# rfob.net
KiCad netlist of a schematic drawn in EAGLE
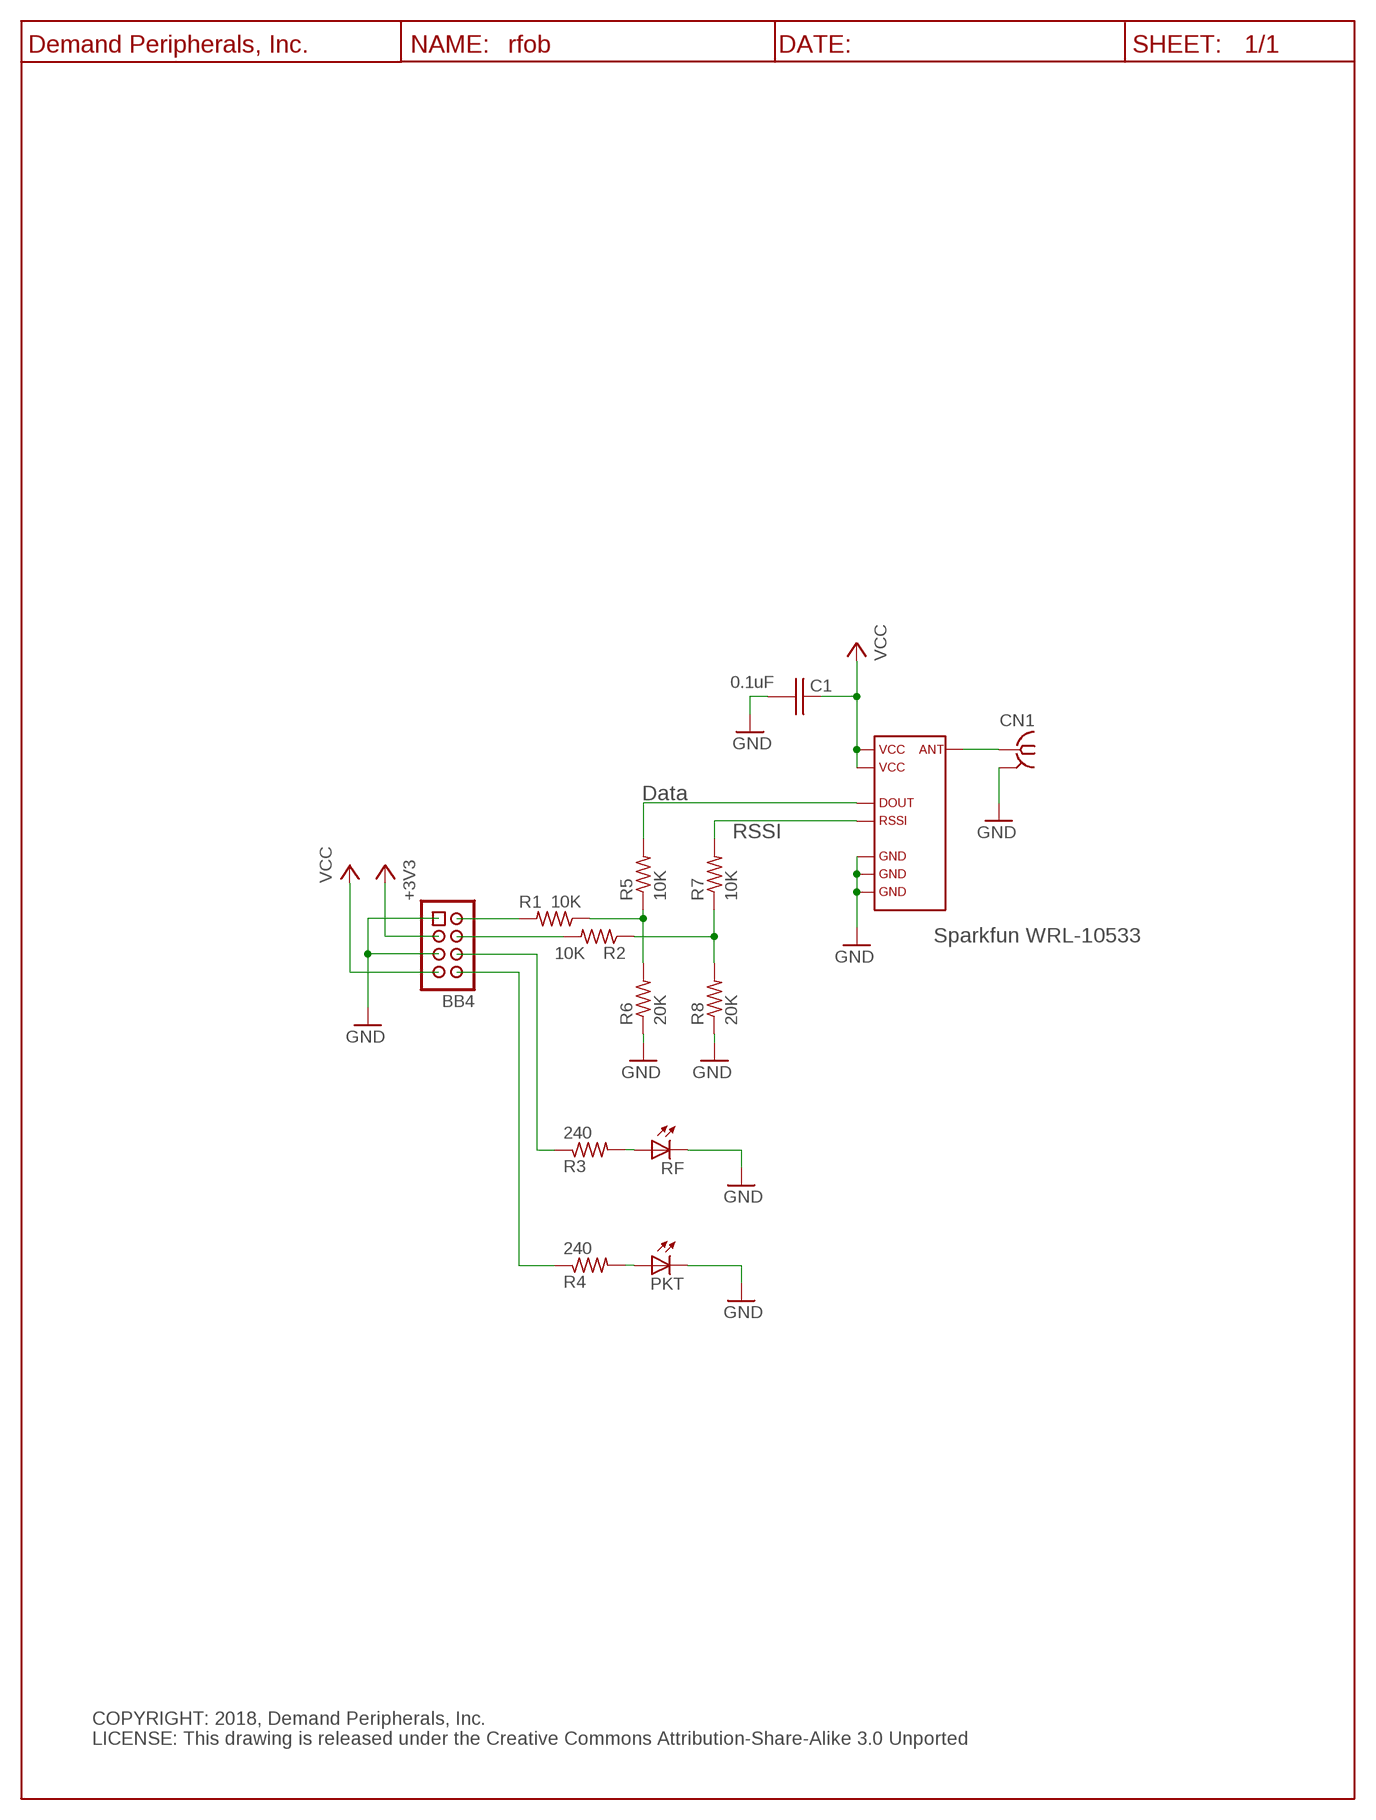
[diagram p0: schematic, sheet 1]

(export (version "E")
  (design (tool "Eeschema 10.0.6"))
  (components
    (comp (ref "BB4")
      (value "Keyed_Pin_Header_4x2(0.1\"x0.1\")")
      (footprint "eagle-import:HDR-4X2")
      (libsource (lib "eagle-import") (part "HDR-4X2-SHR"))
    )
    (comp (ref "C1")
      (value "0.1uF")
      (footprint "eagle-import:C0603")
      (libsource (lib "eagle-import") (part "C0.1UF_C0603"))
    )
    (comp (ref "CN1")
      (value "BU-SMA-V")
      (footprint "eagle-import:BU-SMA-V")
      (libsource (lib "eagle-import") (part "BU-SMA-V"))
    )
    (comp (ref "PKT")
      (value "LED-0805-RED")
      (footprint "eagle-import:0805")
      (libsource (lib "eagle-import") (part "LED-0805-RED"))
    )
    (comp (ref "R1")
      (value "10K")
      (footprint "eagle-import:R0603")
      (libsource (lib "eagle-import") (part "R10K_R0603"))
    )
    (comp (ref "R2")
      (value "10K")
      (footprint "eagle-import:R0603")
      (libsource (lib "eagle-import") (part "R10K_R0603"))
    )
    (comp (ref "R3")
      (value "240")
      (footprint "eagle-import:R0603")
      (libsource (lib "eagle-import") (part "R240_"))
    )
    (comp (ref "R4")
      (value "240")
      (footprint "eagle-import:R0603")
      (libsource (lib "eagle-import") (part "R240_"))
    )
    (comp (ref "R5")
      (value "10K")
      (footprint "eagle-import:R0603")
      (libsource (lib "eagle-import") (part "R10K_R0603"))
    )
    (comp (ref "R6")
      (value "20K")
      (footprint "eagle-import:R0603")
      (libsource (lib "eagle-import") (part "R20K_R0603"))
    )
    (comp (ref "R7")
      (value "10K")
      (footprint "eagle-import:R0603")
      (libsource (lib "eagle-import") (part "R10K_R0603"))
    )
    (comp (ref "R8")
      (value "20K")
      (footprint "eagle-import:R0603")
      (libsource (lib "eagle-import") (part "R20K_R0603"))
    )
    (comp (ref "RF")
      (value "LED-0805-GRN")
      (footprint "eagle-import:0805")
      (libsource (lib "eagle-import") (part "LED-0805-GRN"))
    )
    (comp (ref "RF1")
      (value "RFLINK")
      (footprint "eagle-import:RFLINK")
      (libsource (lib "eagle-import") (part "RFLINK"))
    )
    (comp (ref "U$1")
      (value "DP_FRAME_P")
      (footprint "eagle-import:P_FRAME")
      (libsource (lib "eagle-import") (part "DP_FRAME_P"))
    )
  )
  (nets
    (net (code "1") (name "+3V3") (class "Default")
      (node (ref "BB4") (pin "3") (pinfunction "3_3") (pintype "passive"))
    )
    (net (code "2") (name "GND") (class "Default")
      (node (ref "BB4") (pin "1") (pinfunction "1_1") (pintype "passive"))
      (node (ref "BB4") (pin "5") (pinfunction "5_5") (pintype "passive"))
      (node (ref "C1") (pin "2") (pinfunction "2_2") (pintype "passive"))
      (node (ref "CN1") (pin "2") (pinfunction "2_2") (pintype "passive"))
      (node (ref "CN1") (pin "3") (pinfunction "2_3") (pintype "passive"))
      (node (ref "CN1") (pin "4") (pinfunction "2_4") (pintype "passive"))
      (node (ref "CN1") (pin "5") (pinfunction "2_5") (pintype "passive"))
      (node (ref "PKT") (pin "C") (pinfunction "C_C") (pintype "passive"))
      (node (ref "R6") (pin "1") (pinfunction "1_1") (pintype "passive"))
      (node (ref "R8") (pin "1") (pinfunction "1_1") (pintype "passive"))
      (node (ref "RF") (pin "C") (pinfunction "C_C") (pintype "passive"))
      (node (ref "RF1") (pin "1") (pinfunction "GND1_1") (pintype "open_collector"))
      (node (ref "RF1") (pin "6") (pinfunction "GND3_6") (pintype "open_collector"))
      (node (ref "RF1") (pin "7") (pinfunction "GND2_7") (pintype "open_collector"))
    )
    (net (code "3") (name "Net-(BB4-Pad2)") (class "Default")
      (node (ref "BB4") (pin "2") (pinfunction "2_2") (pintype "passive"))
      (node (ref "R1") (pin "2") (pinfunction "2_2") (pintype "passive"))
    )
    (net (code "4") (name "Net-(BB4-Pad4)") (class "Default")
      (node (ref "BB4") (pin "4") (pinfunction "4_4") (pintype "passive"))
      (node (ref "R2") (pin "2") (pinfunction "2_2") (pintype "passive"))
    )
    (net (code "5") (name "Net-(BB4-Pad6)") (class "Default")
      (node (ref "BB4") (pin "6") (pinfunction "6_6") (pintype "passive"))
      (node (ref "R3") (pin "1") (pinfunction "1_1") (pintype "passive"))
    )
    (net (code "6") (name "Net-(BB4-Pad8)") (class "Default")
      (node (ref "BB4") (pin "8") (pinfunction "8_8") (pintype "passive"))
      (node (ref "R4") (pin "1") (pinfunction "1_1") (pintype "passive"))
    )
    (net (code "7") (name "Net-(PKT-PadA)") (class "Default")
      (node (ref "PKT") (pin "A") (pinfunction "A_A") (pintype "passive"))
      (node (ref "R4") (pin "2") (pinfunction "2_2") (pintype "passive"))
    )
    (net (code "8") (name "Net-(R1-Pad1)") (class "Default")
      (node (ref "R1") (pin "1") (pinfunction "1_1") (pintype "passive"))
      (node (ref "R5") (pin "1") (pinfunction "1_1") (pintype "passive"))
      (node (ref "R6") (pin "2") (pinfunction "2_2") (pintype "passive"))
    )
    (net (code "9") (name "Net-(R2-Pad1)") (class "Default")
      (node (ref "R2") (pin "1") (pinfunction "1_1") (pintype "passive"))
      (node (ref "R7") (pin "1") (pinfunction "1_1") (pintype "passive"))
      (node (ref "R8") (pin "2") (pinfunction "2_2") (pintype "passive"))
    )
    (net (code "10") (name "Net-(R3-Pad2)") (class "Default")
      (node (ref "R3") (pin "2") (pinfunction "2_2") (pintype "passive"))
      (node (ref "RF") (pin "A") (pinfunction "A_A") (pintype "passive"))
    )
    (net (code "11") (name "Net-(RF1-ANT)") (class "Default")
      (node (ref "CN1") (pin "1") (pinfunction "1_1") (pintype "passive"))
      (node (ref "RF1") (pin "8") (pinfunction "ANT_8") (pintype "open_collector"))
    )
    (net (code "12") (name "Net-(RF1-DOUT)") (class "Default")
      (node (ref "R5") (pin "2") (pinfunction "2_2") (pintype "passive"))
      (node (ref "RF1") (pin "2") (pinfunction "DOUT_2") (pintype "open_collector"))
    )
    (net (code "13") (name "Net-(RF1-RSSI)") (class "Default")
      (node (ref "R7") (pin "2") (pinfunction "2_2") (pintype "passive"))
      (node (ref "RF1") (pin "3") (pinfunction "RSSI_3") (pintype "open_collector"))
    )
    (net (code "14") (name "VCC") (class "Default")
      (node (ref "BB4") (pin "7") (pinfunction "7_7") (pintype "passive"))
      (node (ref "C1") (pin "1") (pinfunction "1_1") (pintype "passive"))
      (node (ref "RF1") (pin "4") (pinfunction "VCC1_4") (pintype "open_collector"))
      (node (ref "RF1") (pin "5") (pinfunction "VCC2_5") (pintype "open_collector"))
    )
  )
)
